# Power_distribution2.net
KiCad netlist of a schematic drawn in Altium Designer
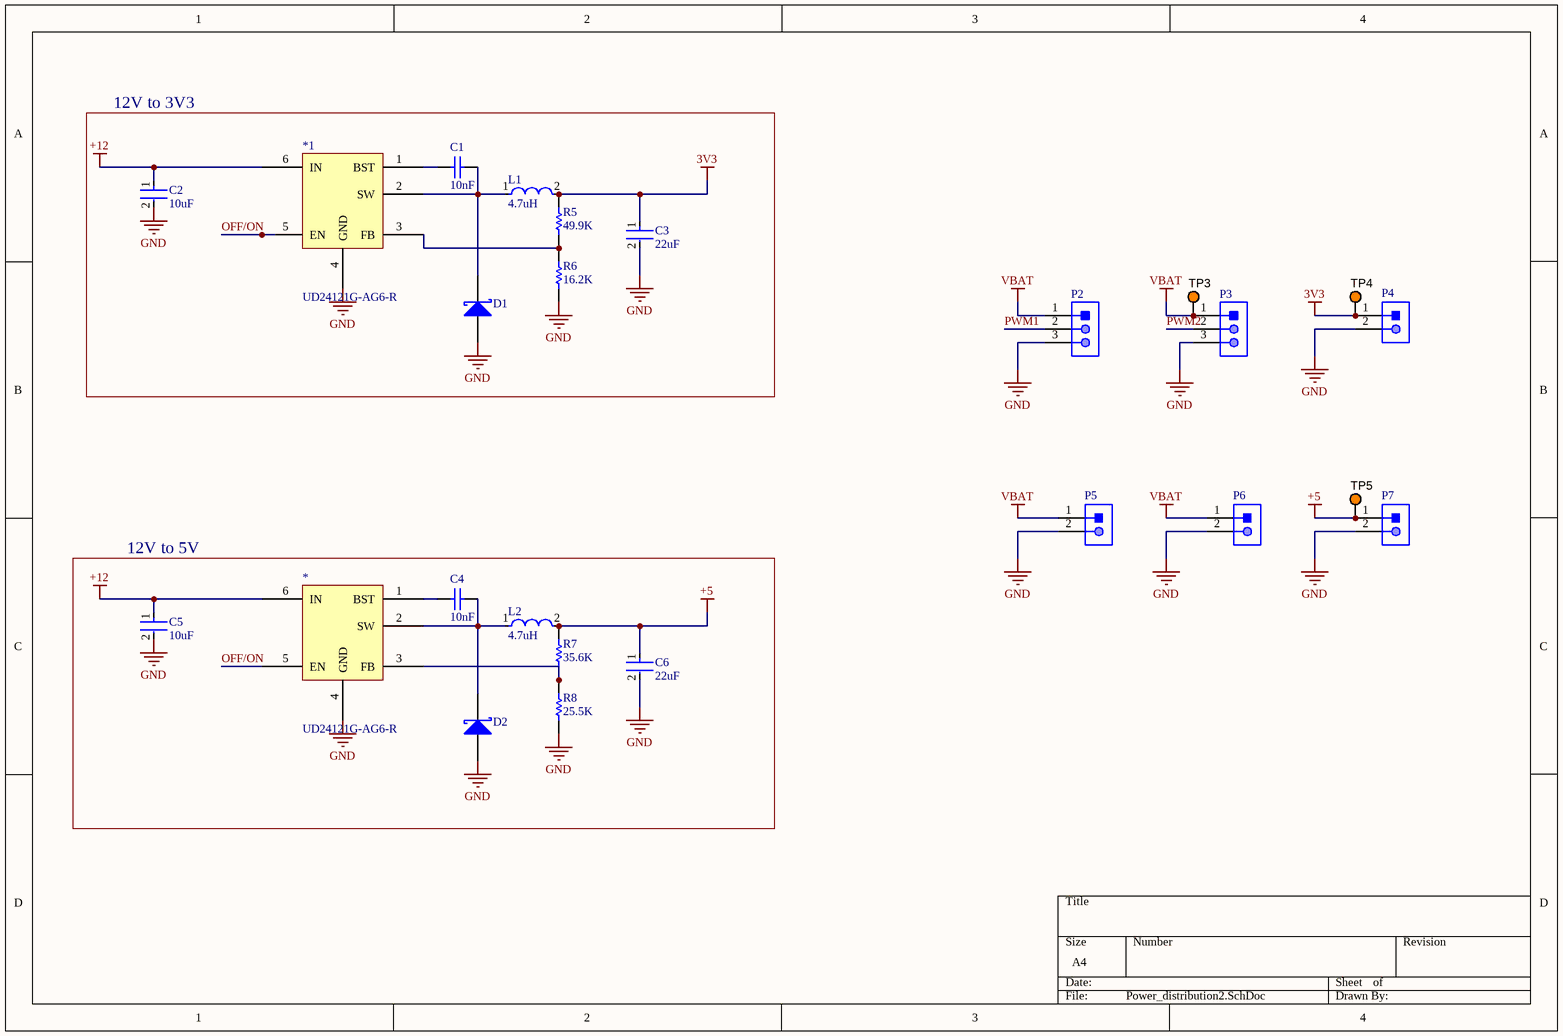
[diagram p0: Power_distribution2.SchDoc]

(export (version "E")
  (design (tool "Eeschema 10.0.6"))
  (components
    (comp (ref "*")
      (value "UD24121G-AG6-R")
      (footprint "SOT95P245X110-6N")
      (libsource (lib "UD24121G-AG6-R") (part "UD24121G-AG6-R"))
    )
    (comp (ref "*1")
      (value "UD24121G-AG6-R")
      (footprint "SOT95P245X110-6N")
      (libsource (lib "UD24121G-AG6-R") (part "UD24121G-AG6-R"))
    )
    (comp (ref "C1")
      (value "10nF")
      (footprint "CAPC1608X90X35ML10T15")
      (description "Chip Capacitor, 10 nF, +/- 10%, 50 V, -55 to 125 degC, 0603 (1608 Metric), RoHS, Tape and Reel")
      (fields (field (name "VOLTAGE") "50V") (field (name "TOLERANCE") "10%"))
      (libsource (lib "Altium Content Vault") (part "CAP-NP-2"))
    )
    (comp (ref "C2")
      (value "10uF")
      (footprint "FP-1210-L_3_3_0_4-W_2_5_0-MFG")
      (description "General Purpose Ceramic Capacitor, 1210, 10uF, 10%, X5R, 15%, 25V")
      (fields (field (name "VOLTAGE") "25V") (field (name "TOLERANCE") "10%"))
      (libsource (lib "Altium Content Vault") (part "b4654b650e69147ec39a6b967a45e02"))
    )
    (comp (ref "C3")
      (value "22uF")
      (footprint "FP-GRM21B-0_15-MFG")
      (description "Chip Multilayer Ceramic Capacitors for General Purpose, 0805, 22uF, X5R, 15%, 20%, 6.3V")
      (fields (field (name "VOLTAGE") "6.3V") (field (name "TOLERANCE") "20%"))
      (libsource (lib "Altium Content Vault") (part "b4654b650e69147ec39a6b967a45e02"))
    )
    (comp (ref "C4")
      (value "10nF")
      (footprint "CAPC1608X90X35ML10T15")
      (description "Chip Capacitor, 10 nF, +/- 10%, 50 V, -55 to 125 degC, 0603 (1608 Metric), RoHS, Tape and Reel")
      (fields (field (name "VOLTAGE") "50V") (field (name "TOLERANCE") "10%"))
      (libsource (lib "Altium Content Vault") (part "CAP-NP-2"))
    )
    (comp (ref "C5")
      (value "10uF")
      (footprint "FP-1210-L_3_3_0_4-W_2_5_0-MFG")
      (description "General Purpose Ceramic Capacitor, 1210, 10uF, 10%, X5R, 15%, 25V")
      (fields (field (name "VOLTAGE") "25V") (field (name "TOLERANCE") "10%"))
      (libsource (lib "Altium Content Vault") (part "b4654b650e69147ec39a6b967a45e02"))
    )
    (comp (ref "C6")
      (value "22uF")
      (footprint "FP-GRM21B-0_15-MFG")
      (description "Chip Multilayer Ceramic Capacitors for General Purpose, 0805, 22uF, X5R, 15%, 20%, 6.3V")
      (fields (field (name "VOLTAGE") "6.3V") (field (name "TOLERANCE") "20%"))
      (libsource (lib "Altium Content Vault") (part "b4654b650e69147ec39a6b967a45e02"))
    )
    (comp (ref "D1")
      (value "B230A-13-F")
      (footprint "DIOD-SMA-2_V")
      (fields (field (name "MANUFACTURER") "Diodes Inc"))
      (libsource (lib "Altium Content Vault") (part "DIOD-DSKY-A1K2-2"))
    )
    (comp (ref "D2")
      (value "B230A-13-F")
      (footprint "DIOD-SMA-2_V")
      (fields (field (name "MANUFACTURER") "Diodes Inc"))
      (libsource (lib "Altium Content Vault") (part "DIOD-DSKY-A1K2-2"))
    )
    (comp (ref "L1")
      (value "4.7uH")
      (footprint "FP-LQH31CN_03-MFG")
      (description "Wire Wound Ferrite Inductor for General Circuits 4.7μH ±10% 2.21Ω 120mA 1206")
      (fields (field (name "TOLERANCE") "10%"))
      (libsource (lib "Altium Content Vault") (part "725321dda6339637d4d059423bc1c3c"))
    )
    (comp (ref "L2")
      (value "4.7uH")
      (footprint "FP-LQH31CN_03-MFG")
      (description "Wire Wound Ferrite Inductor for General Circuits 4.7μH ±10% 2.21Ω 120mA 1206")
      (fields (field (name "TOLERANCE") "10%"))
      (libsource (lib "Altium Content Vault") (part "725321dda6339637d4d059423bc1c3c"))
    )
    (comp (ref "P2")
      (value "B3B-PH-K-S(LF)(SN)")
      (footprint "JST-B3B-PH-K-S-3_V")
      (fields (field (name "MANUFACTURER") "JST"))
      (libsource (lib "Altium Content Vault") (part "CN-1P-M-R3"))
    )
    (comp (ref "P3")
      (value "B3B-PH-K-S(LF)(SN)")
      (footprint "JST-B3B-PH-K-S-3_V")
      (fields (field (name "MANUFACTURER") "JST"))
      (libsource (lib "Altium Content Vault") (part "CN-1P-M-R3"))
    )
    (comp (ref "P4")
      (value "S2B-PH-K-S(LF)(SN)")
      (footprint "JST-S2B-PH-K-S_V")
      (fields (field (name "TOLERANCE") "20%"))
      (libsource (lib "Altium Content Vault") (part "CN-1P-M-R2"))
    )
    (comp (ref "P5")
      (value "S2B-PH-K-S(LF)(SN)")
      (footprint "JST-S2B-PH-K-S_V")
      (fields (field (name "TOLERANCE") "20%"))
      (libsource (lib "Altium Content Vault") (part "CN-1P-M-R2"))
    )
    (comp (ref "P6")
      (value "S2B-PH-K-S(LF)(SN)")
      (footprint "JST-S2B-PH-K-S_V")
      (fields (field (name "TOLERANCE") "20%"))
      (libsource (lib "Altium Content Vault") (part "CN-1P-M-R2"))
    )
    (comp (ref "P7")
      (value "S2B-PH-K-S(LF)(SN)")
      (footprint "JST-S2B-PH-K-S_V")
      (fields (field (name "TOLERANCE") "20%"))
      (libsource (lib "Altium Content Vault") (part "CN-1P-M-R2"))
    )
    (comp (ref "R5")
      (value "49.9K")
      (footprint "RESC1005X40X25LL05T05")
      (description "Chip Resistor, 49.9 KOhm, +/- 1%, 100 mW, -55 to 155 degC, 0402 (1005 Metric), RoHS, Tape and Reel")
      (fields (field (name "MANUFACTURER") "Basic Passives") (field (name "PARTNUMBER") "ERJ-2RKF4992X"))
      (libsource (lib "Altium Content Vault") (part "RES-2"))
    )
    (comp (ref "R6")
      (value "16.2K")
      (footprint "RESC2013X50X30NL20T20")
      (fields (field (name "PART NUMBER") "CRCW080516K2FKEA") (field (name "MANUFACTURER") "Vishay Dale"))
      (libsource (lib "Altium Content Vault") (part "RES"))
    )
    (comp (ref "R7")
      (value "35.6K")
      (footprint "RESC1005X40X25LL05T05")
      (description "Chip Resistor, 49.9 KOhm, +/- 1%, 100 mW, -55 to 155 degC, 0402 (1005 Metric), RoHS, Tape and Reel")
      (fields (field (name "MANUFACTURER") "Basic Passives") (field (name "PARTNUMBER") "ERJ-2RKF4992X"))
      (libsource (lib "Altium Content Vault") (part "RES-2"))
    )
    (comp (ref "R8")
      (value "25.5K")
      (footprint "RESC2013X50X30NL20T20")
      (fields (field (name "PART NUMBER") "CRCW080516K2FKEA") (field (name "MANUFACTURER") "Vishay Dale"))
      (libsource (lib "Altium Content Vault") (part "RES"))
    )
    (comp (ref "TP3")
      (value "5003")
      (footprint "KSTN-5003")
      (description "Test Point, Orange, 1-Pin THD, RoHS")
      (libsource (lib "Altium Content Vault") (part "TESTPOINT_ORANGE"))
    )
    (comp (ref "TP4")
      (value "5003")
      (footprint "KSTN-5003")
      (description "Test Point, Orange, 1-Pin THD, RoHS")
      (libsource (lib "Altium Content Vault") (part "TESTPOINT_ORANGE"))
    )
    (comp (ref "TP5")
      (value "5003")
      (footprint "KSTN-5003")
      (description "Test Point, Orange, 1-Pin THD, RoHS")
      (libsource (lib "Altium Content Vault") (part "TESTPOINT_ORANGE"))
    )
  )
  (nets
    (net (code "1") (name "+5") (class "Default")
      (node (ref "C6") (pin "1") (pinfunction "1_1") (pintype "passive"))
      (node (ref "L2") (pin "2") (pinfunction "2_2") (pintype "passive"))
      (node (ref "P7") (pin "1") (pinfunction "1_1") (pintype "passive"))
      (node (ref "R7") (pin "2") (pinfunction "2_2") (pintype "passive"))
      (node (ref "TP5") (pin "1") (pinfunction "1_1") (pintype "passive"))
    )
    (net (code "2") (name "+12") (class "Default")
      (node (ref "*") (pin "6") (pinfunction "IN_6") (pintype "passive"))
      (node (ref "*1") (pin "6") (pinfunction "IN_6") (pintype "passive"))
      (node (ref "C2") (pin "1") (pinfunction "1_1") (pintype "passive"))
      (node (ref "C5") (pin "1") (pinfunction "1_1") (pintype "passive"))
    )
    (net (code "3") (name "/OFF{slash}ON") (class "Default")
      (node (ref "*") (pin "5") (pinfunction "EN_5") (pintype "passive"))
      (node (ref "*1") (pin "5") (pinfunction "EN_5") (pintype "passive"))
    )
    (net (code "4") (name "/PWM1") (class "Default")
      (node (ref "P2") (pin "2") (pinfunction "2_2") (pintype "passive"))
    )
    (net (code "5") (name "/PWM2") (class "Default")
      (node (ref "P3") (pin "2") (pinfunction "2_2") (pintype "passive"))
    )
    (net (code "6") (name "3V3") (class "Default")
      (node (ref "C3") (pin "1") (pinfunction "1_1") (pintype "passive"))
      (node (ref "L1") (pin "2") (pinfunction "2_2") (pintype "passive"))
      (node (ref "P4") (pin "1") (pinfunction "1_1") (pintype "passive"))
      (node (ref "R5") (pin "2") (pinfunction "2_2") (pintype "passive"))
      (node (ref "TP4") (pin "1") (pinfunction "1_1") (pintype "passive"))
    )
    (net (code "7") (name "GND") (class "Default")
      (node (ref "*") (pin "4") (pinfunction "GND_4") (pintype "passive"))
      (node (ref "*1") (pin "4") (pinfunction "GND_4") (pintype "passive"))
      (node (ref "C2") (pin "2") (pinfunction "2_2") (pintype "passive"))
      (node (ref "C3") (pin "2") (pinfunction "2_2") (pintype "passive"))
      (node (ref "C5") (pin "2") (pinfunction "2_2") (pintype "passive"))
      (node (ref "C6") (pin "2") (pinfunction "2_2") (pintype "passive"))
      (node (ref "D1") (pin "1") (pinfunction "A_1") (pintype "passive"))
      (node (ref "D2") (pin "1") (pinfunction "A_1") (pintype "passive"))
      (node (ref "P2") (pin "3") (pinfunction "3_3") (pintype "passive"))
      (node (ref "P3") (pin "3") (pinfunction "3_3") (pintype "passive"))
      (node (ref "P4") (pin "2") (pinfunction "2_2") (pintype "passive"))
      (node (ref "P5") (pin "2") (pinfunction "2_2") (pintype "passive"))
      (node (ref "P6") (pin "2") (pinfunction "2_2") (pintype "passive"))
      (node (ref "P7") (pin "2") (pinfunction "2_2") (pintype "passive"))
      (node (ref "R6") (pin "1") (pinfunction "1_1") (pintype "passive"))
      (node (ref "R8") (pin "1") (pinfunction "1_1") (pintype "passive"))
    )
    (net (code "8") (name "Net-(*-BST)") (class "Default")
      (node (ref "*") (pin "1") (pinfunction "BST_1") (pintype "passive"))
      (node (ref "C4") (pin "1") (pinfunction "1_1") (pintype "passive"))
    )
    (net (code "9") (name "Net-(*-FB)") (class "Default")
      (node (ref "*") (pin "3") (pinfunction "FB_3") (pintype "passive"))
      (node (ref "R7") (pin "1") (pinfunction "1_1") (pintype "passive"))
      (node (ref "R8") (pin "2") (pinfunction "2_2") (pintype "passive"))
    )
    (net (code "10") (name "Net-(*-SW)") (class "Default")
      (node (ref "*") (pin "2") (pinfunction "SW_2") (pintype "passive"))
      (node (ref "C4") (pin "2") (pinfunction "2_2") (pintype "passive"))
      (node (ref "D2") (pin "2") (pinfunction "K_2") (pintype "passive"))
      (node (ref "L2") (pin "1") (pinfunction "1_1") (pintype "passive"))
    )
    (net (code "11") (name "Net-(*1-BST)") (class "Default")
      (node (ref "*1") (pin "1") (pinfunction "BST_1") (pintype "passive"))
      (node (ref "C1") (pin "1") (pinfunction "1_1") (pintype "passive"))
    )
    (net (code "12") (name "Net-(*1-FB)") (class "Default")
      (node (ref "*1") (pin "3") (pinfunction "FB_3") (pintype "passive"))
      (node (ref "R5") (pin "1") (pinfunction "1_1") (pintype "passive"))
      (node (ref "R6") (pin "2") (pinfunction "2_2") (pintype "passive"))
    )
    (net (code "13") (name "Net-(*1-SW)") (class "Default")
      (node (ref "*1") (pin "2") (pinfunction "SW_2") (pintype "passive"))
      (node (ref "C1") (pin "2") (pinfunction "2_2") (pintype "passive"))
      (node (ref "D1") (pin "2") (pinfunction "K_2") (pintype "passive"))
      (node (ref "L1") (pin "1") (pinfunction "1_1") (pintype "passive"))
    )
    (net (code "14") (name "VBAT") (class "Default")
      (node (ref "P2") (pin "1") (pinfunction "1_1") (pintype "passive"))
      (node (ref "P3") (pin "1") (pinfunction "1_1") (pintype "passive"))
      (node (ref "P5") (pin "1") (pinfunction "1_1") (pintype "passive"))
      (node (ref "P6") (pin "1") (pinfunction "1_1") (pintype "passive"))
      (node (ref "TP3") (pin "1") (pinfunction "1_1") (pintype "passive"))
    )
  )
)
